# 2x8_To_1x16.net
KiCad netlist of a schematic drawn in EAGLE
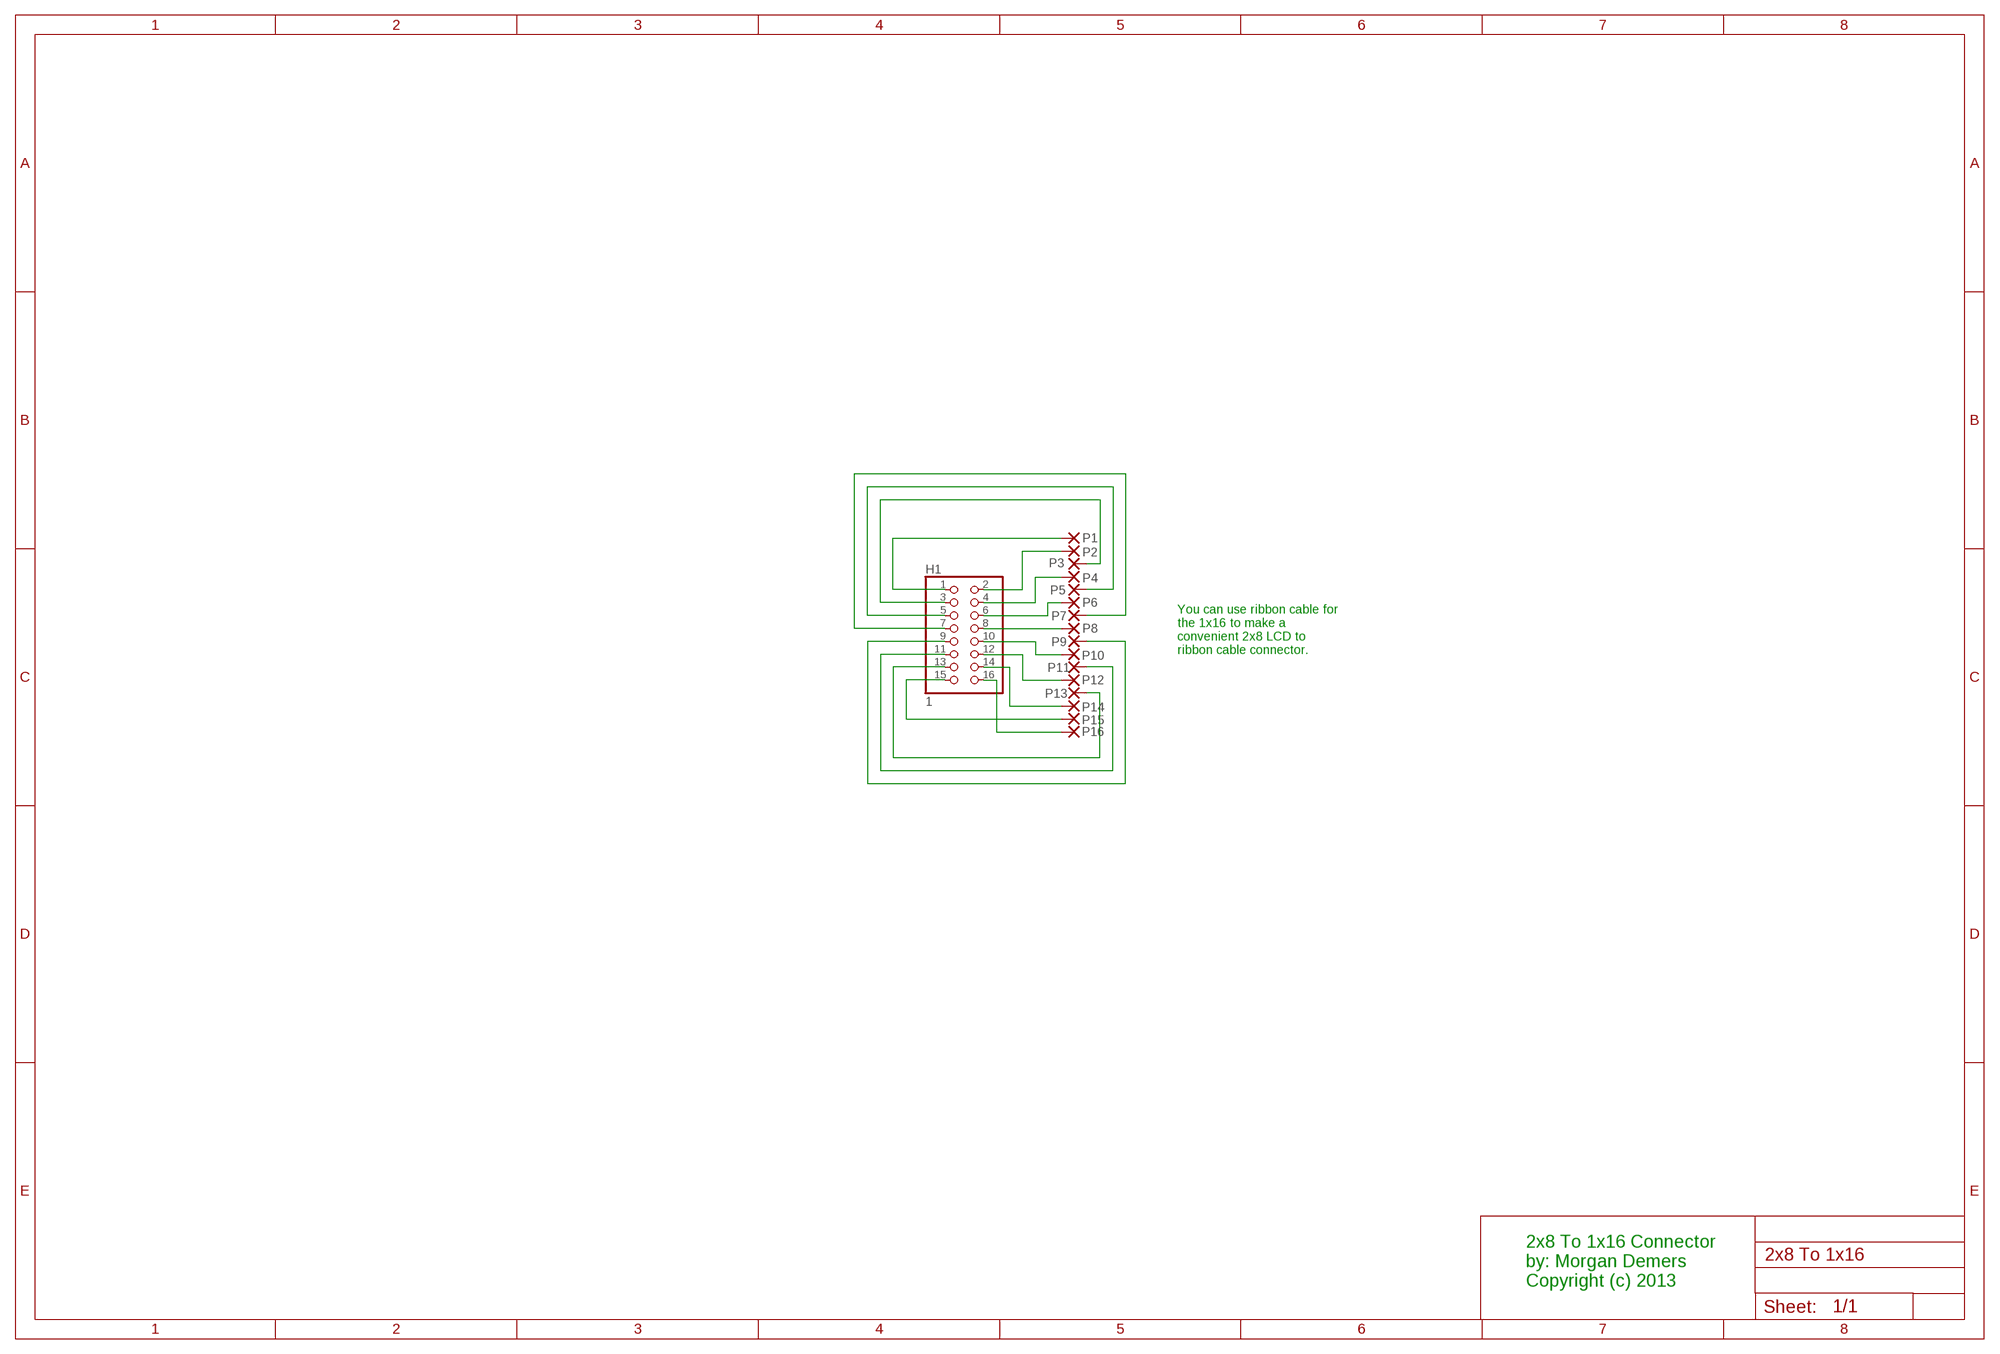
[diagram p0: schematic, sheet 1]

(export (version "E")
  (design (tool "Eeschema 10.0.6"))
  (components
    (comp (ref "H1")
      (value "1")
      (footprint "eagle-import:2X08")
      (libsource (lib "eagle-import") (part "PINHD-2X8"))
    )
    (comp (ref "P1")
      (value "1,6/0,9")
      (footprint "eagle-import:1,6_0,9")
      (libsource (lib "eagle-import") (part "1,6/0,9"))
    )
    (comp (ref "P2")
      (value "1,6/0,9")
      (footprint "eagle-import:1,6_0,9")
      (libsource (lib "eagle-import") (part "1,6/0,9"))
    )
    (comp (ref "P3")
      (value "1,6/0,9")
      (footprint "eagle-import:1,6_0,9")
      (libsource (lib "eagle-import") (part "1,6/0,9"))
    )
    (comp (ref "P4")
      (value "1,6/0,9")
      (footprint "eagle-import:1,6_0,9")
      (libsource (lib "eagle-import") (part "1,6/0,9"))
    )
    (comp (ref "P5")
      (value "1,6/0,9")
      (footprint "eagle-import:1,6_0,9")
      (libsource (lib "eagle-import") (part "1,6/0,9"))
    )
    (comp (ref "P6")
      (value "1,6/0,9")
      (footprint "eagle-import:1,6_0,9")
      (libsource (lib "eagle-import") (part "1,6/0,9"))
    )
    (comp (ref "P7")
      (value "1,6/0,9")
      (footprint "eagle-import:1,6_0,9")
      (libsource (lib "eagle-import") (part "1,6/0,9"))
    )
    (comp (ref "P8")
      (value "1,6/0,9")
      (footprint "eagle-import:1,6_0,9")
      (libsource (lib "eagle-import") (part "1,6/0,9"))
    )
    (comp (ref "P9")
      (value "1,6/0,9")
      (footprint "eagle-import:1,6_0,9")
      (libsource (lib "eagle-import") (part "1,6/0,9"))
    )
    (comp (ref "P10")
      (value "1,6/0,9")
      (footprint "eagle-import:1,6_0,9")
      (libsource (lib "eagle-import") (part "1,6/0,9"))
    )
    (comp (ref "P11")
      (value "1,6/0,9")
      (footprint "eagle-import:1,6_0,9")
      (libsource (lib "eagle-import") (part "1,6/0,9"))
    )
    (comp (ref "P12")
      (value "1,6/0,9")
      (footprint "eagle-import:1,6_0,9")
      (libsource (lib "eagle-import") (part "1,6/0,9"))
    )
    (comp (ref "P13")
      (value "1,6/0,9")
      (footprint "eagle-import:1,6_0,9")
      (libsource (lib "eagle-import") (part "1,6/0,9"))
    )
    (comp (ref "P14")
      (value "1,6/0,9")
      (footprint "eagle-import:1,6_0,9")
      (libsource (lib "eagle-import") (part "1,6/0,9"))
    )
    (comp (ref "P15")
      (value "1,6/0,9")
      (footprint "eagle-import:1,6_0,9")
      (libsource (lib "eagle-import") (part "1,6/0,9"))
    )
    (comp (ref "P16")
      (value "1,6/0,9")
      (footprint "eagle-import:1,6_0,9")
      (libsource (lib "eagle-import") (part "1,6/0,9"))
    )
  )
  (nets
    (net (code "1") (name "Net-(P1-P)") (class "Default")
      (node (ref "H1") (pin "1") (pinfunction "1_1") (pintype "passive"))
      (node (ref "P1") (pin "1") (pinfunction "P_1") (pintype "passive"))
    )
    (net (code "2") (name "Net-(P2-P)") (class "Default")
      (node (ref "H1") (pin "2") (pinfunction "2_2") (pintype "passive"))
      (node (ref "P2") (pin "1") (pinfunction "P_1") (pintype "passive"))
    )
    (net (code "3") (name "Net-(P3-P)") (class "Default")
      (node (ref "H1") (pin "3") (pinfunction "3_3") (pintype "passive"))
      (node (ref "P3") (pin "1") (pinfunction "P_1") (pintype "passive"))
    )
    (net (code "4") (name "Net-(P4-P)") (class "Default")
      (node (ref "H1") (pin "4") (pinfunction "4_4") (pintype "passive"))
      (node (ref "P4") (pin "1") (pinfunction "P_1") (pintype "passive"))
    )
    (net (code "5") (name "Net-(P5-P)") (class "Default")
      (node (ref "H1") (pin "5") (pinfunction "5_5") (pintype "passive"))
      (node (ref "P5") (pin "1") (pinfunction "P_1") (pintype "passive"))
    )
    (net (code "6") (name "Net-(P6-P)") (class "Default")
      (node (ref "H1") (pin "6") (pinfunction "6_6") (pintype "passive"))
      (node (ref "P6") (pin "1") (pinfunction "P_1") (pintype "passive"))
    )
    (net (code "7") (name "Net-(P7-P)") (class "Default")
      (node (ref "H1") (pin "7") (pinfunction "7_7") (pintype "passive"))
      (node (ref "P7") (pin "1") (pinfunction "P_1") (pintype "passive"))
    )
    (net (code "8") (name "Net-(P8-P)") (class "Default")
      (node (ref "H1") (pin "8") (pinfunction "8_8") (pintype "passive"))
      (node (ref "P8") (pin "1") (pinfunction "P_1") (pintype "passive"))
    )
    (net (code "9") (name "Net-(P9-P)") (class "Default")
      (node (ref "H1") (pin "9") (pinfunction "9_9") (pintype "passive"))
      (node (ref "P9") (pin "1") (pinfunction "P_1") (pintype "passive"))
    )
    (net (code "10") (name "Net-(P10-P)") (class "Default")
      (node (ref "H1") (pin "10") (pinfunction "10_10") (pintype "passive"))
      (node (ref "P10") (pin "1") (pinfunction "P_1") (pintype "passive"))
    )
    (net (code "11") (name "Net-(P11-P)") (class "Default")
      (node (ref "H1") (pin "11") (pinfunction "11_11") (pintype "passive"))
      (node (ref "P11") (pin "1") (pinfunction "P_1") (pintype "passive"))
    )
    (net (code "12") (name "Net-(P12-P)") (class "Default")
      (node (ref "H1") (pin "12") (pinfunction "12_12") (pintype "passive"))
      (node (ref "P12") (pin "1") (pinfunction "P_1") (pintype "passive"))
    )
    (net (code "13") (name "Net-(P13-P)") (class "Default")
      (node (ref "H1") (pin "13") (pinfunction "13_13") (pintype "passive"))
      (node (ref "P13") (pin "1") (pinfunction "P_1") (pintype "passive"))
    )
    (net (code "14") (name "Net-(P14-P)") (class "Default")
      (node (ref "H1") (pin "14") (pinfunction "14_14") (pintype "passive"))
      (node (ref "P14") (pin "1") (pinfunction "P_1") (pintype "passive"))
    )
    (net (code "15") (name "Net-(P15-P)") (class "Default")
      (node (ref "H1") (pin "15") (pinfunction "15_15") (pintype "passive"))
      (node (ref "P15") (pin "1") (pinfunction "P_1") (pintype "passive"))
    )
    (net (code "16") (name "Net-(P16-P)") (class "Default")
      (node (ref "H1") (pin "16") (pinfunction "16_16") (pintype "passive"))
      (node (ref "P16") (pin "1") (pinfunction "P_1") (pintype "passive"))
    )
  )
)
